# 02-USER_IO.net
KiCad netlist of a schematic drawn in Altium Designer
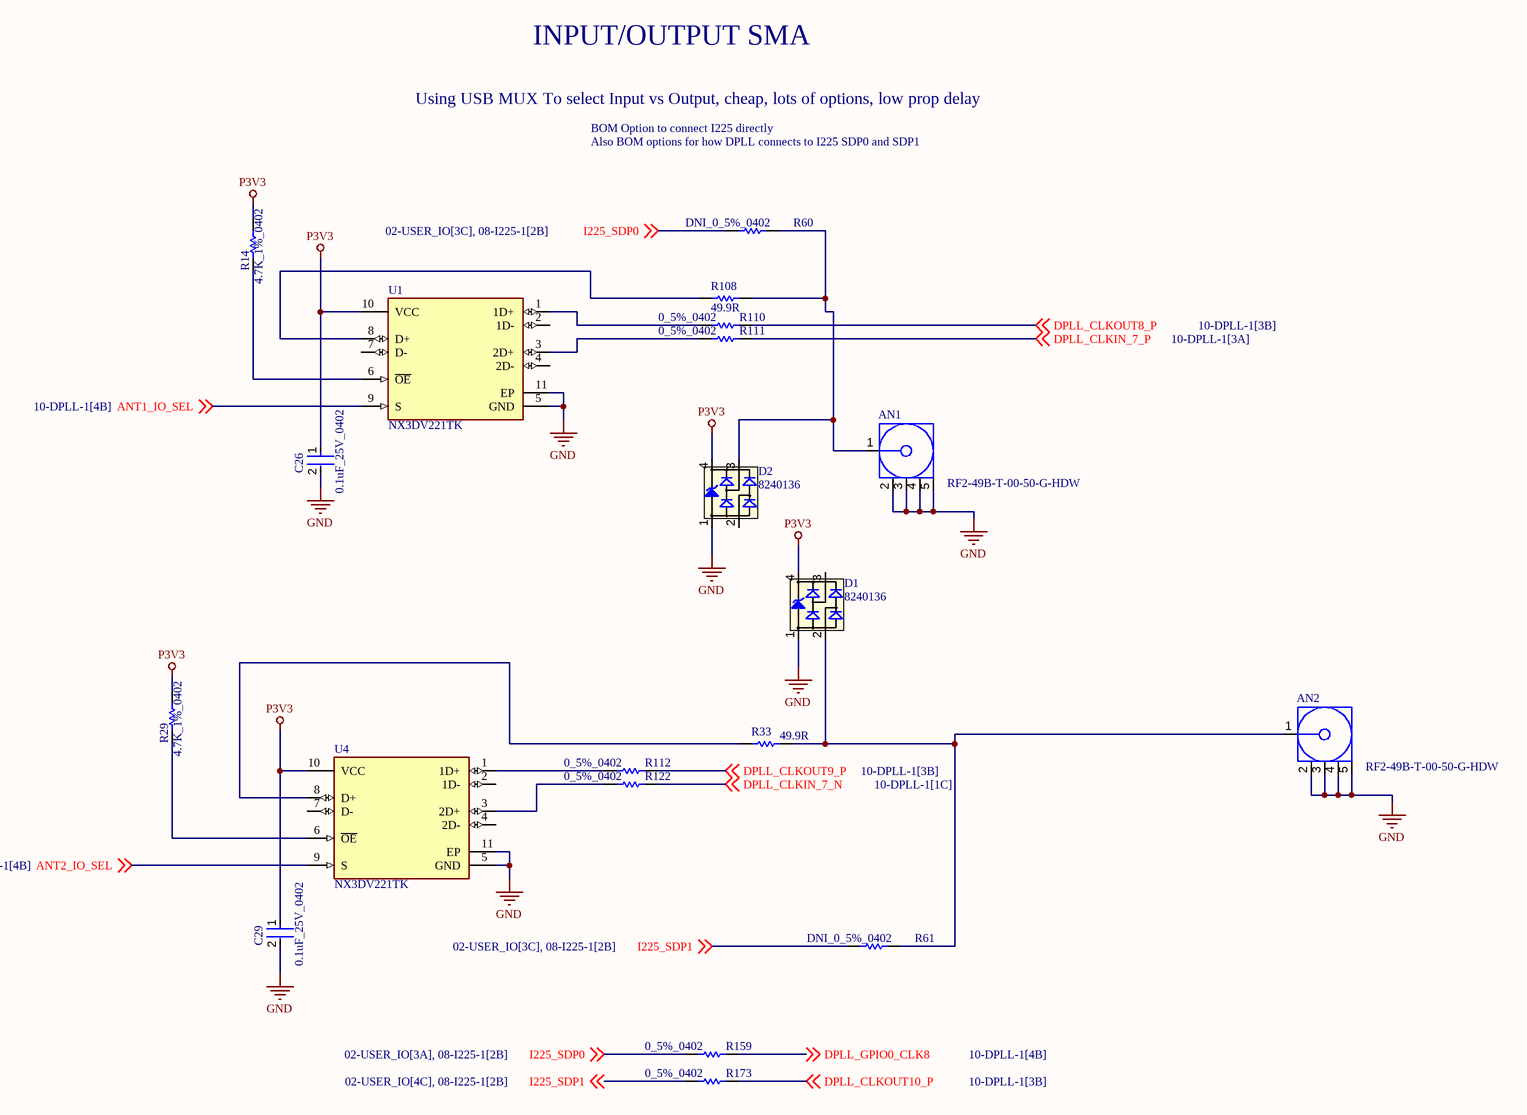
[diagram p0: 02-USER_IO.SchDoc]

(export (version "E")
  (design (tool "Eeschema 10.0.6"))
  (components
    (comp (ref "AN1")
      (value "RF2-49B-T-00-50-G-HDW")
      (footprint "AMPH-901-143-6RFX_V")
      (description "Coaxial connector, 50 Ohm, -65 to 165 degC, 5-Pin THD, RoHS, Bulk")
      (fields (field (name "MANUFACTURER") "Amphenol"))
      (libsource (lib "Altium Content Vault") (part "CN-S-4F-RF5"))
    )
    (comp (ref "AN2")
      (value "RF2-49B-T-00-50-G-HDW")
      (footprint "AMPH-901-143-6RFX_V")
      (description "Coaxial connector, 50 Ohm, -65 to 165 degC, 5-Pin THD, RoHS, Bulk")
      (fields (field (name "MANUFACTURER") "Amphenol"))
      (libsource (lib "Altium Content Vault") (part "CN-S-4F-RF5"))
    )
    (comp (ref "C26")
      (value "0.1uF_25V_0402")
      (footprint "FP-0402-L_1_0_1-W_0_5_0_1-IPC_C")
      (description "General Purpose Ceramic Capacitor, 0402, 100nF, 10%, X7R, 15%, 25V")
      (fields (field (name "VOLTAGE") "25V") (field (name "TOLERANCE") "10%"))
      (libsource (lib "Altium Content Vault") (part "b4654b650e69147ec39a6b967a45e02"))
    )
    (comp (ref "C29")
      (value "0.1uF_25V_0402")
      (footprint "FP-0402-L_1_0_1-W_0_5_0_1-IPC_C")
      (description "General Purpose Ceramic Capacitor, 0402, 100nF, 10%, X7R, 15%, 25V")
      (fields (field (name "VOLTAGE") "25V") (field (name "TOLERANCE") "10%"))
      (libsource (lib "Altium Content Vault") (part "b4654b650e69147ec39a6b967a45e02"))
    )
    (comp (ref "D1")
      (value "8240136")
      (footprint "SOT143-4L")
      (description "TVS Diode WE-TVS-HS, VRWM=3.3V")
      (fields (field (name "MANUFACTURER") "Wuerth Elektronik"))
      (libsource (lib "Altium Content Vault") (part "WE-TVS-HS-4"))
    )
    (comp (ref "D2")
      (value "8240136")
      (footprint "SOT143-4L")
      (description "TVS Diode WE-TVS-HS, VRWM=3.3V")
      (fields (field (name "MANUFACTURER") "Wuerth Elektronik"))
      (libsource (lib "Altium Content Vault") (part "WE-TVS-HS-4"))
    )
    (comp (ref "R14")
      (value "4.7K_1%_0402")
      (footprint "RESC1005X40X25NL10T10")
      (fields (field (name "MANUFACTURER") "Bourns") (field (name "PART NUMBER") "CR0402-FX-4701GLF"))
      (libsource (lib "Altium Content Vault") (part "RES"))
    )
    (comp (ref "R29")
      (value "4.7K_1%_0402")
      (footprint "RESC1005X40X25NL10T10")
      (fields (field (name "MANUFACTURER") "Bourns") (field (name "PART NUMBER") "CR0402-FX-4701GLF"))
      (libsource (lib "Altium Content Vault") (part "RES"))
    )
    (comp (ref "R33")
      (value "49.9R")
      (footprint "RESC1608X55X25NL10T15")
      (libsource (lib "Altium Content Vault") (part "RES-2"))
    )
    (comp (ref "R60")
      (value "DNI_0_5%_0402")
      (footprint "RESC1005X40X25LL10T10")
      (fields (field (name "MANUFACTURER") "KOA Speer") (field (name "PART NUMBER") "RK73Z1ETTP"))
      (libsource (lib "Altium Content Vault") (part "RES"))
    )
    (comp (ref "R61")
      (value "DNI_0_5%_0402")
      (footprint "RESC1005X40X25LL10T10")
      (fields (field (name "MANUFACTURER") "KOA Speer") (field (name "PART NUMBER") "RK73Z1ETTP"))
      (libsource (lib "Altium Content Vault") (part "RES"))
    )
    (comp (ref "R108")
      (value "49.9R")
      (footprint "RESC1608X55X25NL10T15")
      (libsource (lib "Altium Content Vault") (part "RES-2"))
    )
    (comp (ref "R110")
      (value "0_5%_0402")
      (footprint "RESC1005X40X25LL10T10")
      (fields (field (name "MANUFACTURER") "KOA Speer") (field (name "PART NUMBER") "RK73Z1ETTP"))
      (libsource (lib "Altium Content Vault") (part "RES"))
    )
    (comp (ref "R111")
      (value "0_5%_0402")
      (footprint "RESC1005X40X25LL10T10")
      (fields (field (name "MANUFACTURER") "KOA Speer") (field (name "PART NUMBER") "RK73Z1ETTP"))
      (libsource (lib "Altium Content Vault") (part "RES"))
    )
    (comp (ref "R112")
      (value "0_5%_0402")
      (footprint "RESC1005X40X25LL10T10")
      (fields (field (name "MANUFACTURER") "KOA Speer") (field (name "PART NUMBER") "RK73Z1ETTP"))
      (libsource (lib "Altium Content Vault") (part "RES"))
    )
    (comp (ref "R122")
      (value "0_5%_0402")
      (footprint "RESC1005X40X25LL10T10")
      (fields (field (name "MANUFACTURER") "KOA Speer") (field (name "PART NUMBER") "RK73Z1ETTP"))
      (libsource (lib "Altium Content Vault") (part "RES"))
    )
    (comp (ref "R159")
      (value "0_5%_0402")
      (footprint "RESC1005X40X25LL10T10")
      (fields (field (name "MANUFACTURER") "KOA Speer") (field (name "PART NUMBER") "RK73Z1ETTP"))
      (libsource (lib "Altium Content Vault") (part "RES"))
    )
    (comp (ref "R173")
      (value "0_5%_0402")
      (footprint "RESC1005X40X25LL10T10")
      (fields (field (name "MANUFACTURER") "KOA Speer") (field (name "PART NUMBER") "RK73Z1ETTP"))
      (libsource (lib "Altium Content Vault") (part "RES"))
    )
    (comp (ref "U1")
      (value "NX3DV221TK")
      (footprint "FP-SOT650-2-MFG")
      (description "USB Switch IC 1 Channel 10-HVSON (3x3)")
      (libsource (lib "Altium Content Vault") (part "bce77ec48a709d17f0bdc2c26d779bf"))
    )
    (comp (ref "U4")
      (value "NX3DV221TK")
      (footprint "FP-SOT650-2-MFG")
      (description "USB Switch IC 1 Channel 10-HVSON (3x3)")
      (libsource (lib "Altium Content Vault") (part "bce77ec48a709d17f0bdc2c26d779bf"))
    )
  )
  (nets
    (net (code "1") (name "ANT1_IO_SEL") (class "Default")
      (node (ref "U1") (pin "9") (pinfunction "S_9") (pintype "input"))
    )
    (net (code "2") (name "ANT2_IO_SEL") (class "Default")
      (node (ref "U4") (pin "9") (pinfunction "S_9") (pintype "input"))
    )
    (net (code "3") (name "DPLL_CLKIN_7_N") (class "Default")
      (node (ref "R122") (pin "2") (pinfunction "2_2") (pintype "passive"))
    )
    (net (code "4") (name "DPLL_CLKIN_7_P") (class "Default")
      (node (ref "R111") (pin "2") (pinfunction "2_2") (pintype "passive"))
    )
    (net (code "5") (name "DPLL_CLKOUT8_P") (class "Default")
      (node (ref "R110") (pin "2") (pinfunction "2_2") (pintype "passive"))
    )
    (net (code "6") (name "DPLL_CLKOUT9_P") (class "Default")
      (node (ref "R112") (pin "2") (pinfunction "2_2") (pintype "passive"))
    )
    (net (code "7") (name "DPLL_CLKOUT10_P") (class "Default")
      (node (ref "R173") (pin "2") (pinfunction "2_2") (pintype "passive"))
    )
    (net (code "8") (name "DPLL_GPIO0_CLK8") (class "Default")
      (node (ref "R159") (pin "2") (pinfunction "2_2") (pintype "passive"))
    )
    (net (code "9") (name "GND") (class "Default")
      (node (ref "AN1") (pin "2") (pinfunction "2_2") (pintype "passive"))
      (node (ref "AN1") (pin "3") (pinfunction "3_3") (pintype "passive"))
      (node (ref "AN1") (pin "4") (pinfunction "4_4") (pintype "passive"))
      (node (ref "AN1") (pin "5") (pinfunction "5_5") (pintype "passive"))
      (node (ref "AN2") (pin "2") (pinfunction "2_2") (pintype "passive"))
      (node (ref "AN2") (pin "3") (pinfunction "3_3") (pintype "passive"))
      (node (ref "AN2") (pin "4") (pinfunction "4_4") (pintype "passive"))
      (node (ref "AN2") (pin "5") (pinfunction "5_5") (pintype "passive"))
      (node (ref "C26") (pin "2") (pinfunction "2_2") (pintype "passive"))
      (node (ref "C29") (pin "2") (pinfunction "2_2") (pintype "passive"))
      (node (ref "D1") (pin "1") (pinfunction "GND_1") (pintype "passive"))
      (node (ref "D2") (pin "1") (pinfunction "GND_1") (pintype "passive"))
      (node (ref "U1") (pin "11") (pinfunction "EP_11") (pintype "passive"))
      (node (ref "U1") (pin "5") (pinfunction "GND_5") (pintype "power_in"))
      (node (ref "U4") (pin "11") (pinfunction "EP_11") (pintype "passive"))
      (node (ref "U4") (pin "5") (pinfunction "GND_5") (pintype "power_in"))
    )
    (net (code "10") (name "I225_SDP0") (class "Default")
      (node (ref "R159") (pin "1") (pinfunction "1_1") (pintype "passive"))
      (node (ref "R60") (pin "1") (pinfunction "1_1") (pintype "passive"))
    )
    (net (code "11") (name "I225_SDP1") (class "Default")
      (node (ref "R173") (pin "1") (pinfunction "1_1") (pintype "passive"))
      (node (ref "R61") (pin "1") (pinfunction "1_1") (pintype "passive"))
    )
    (net (code "12") (name "Net-(D1-I{slash}O1)") (class "Default")
      (node (ref "AN2") (pin "1") (pinfunction "1_1") (pintype "passive"))
      (node (ref "D1") (pin "2") (pinfunction "I/O1_2") (pintype "passive"))
      (node (ref "R33") (pin "2") (pinfunction "2_2") (pintype "passive"))
      (node (ref "R61") (pin "2") (pinfunction "2_2") (pintype "passive"))
    )
    (net (code "13") (name "Net-(D2-I{slash}O2)") (class "Default")
      (node (ref "AN1") (pin "1") (pinfunction "1_1") (pintype "passive"))
      (node (ref "D2") (pin "3") (pinfunction "I/O2_3") (pintype "passive"))
      (node (ref "R108") (pin "1") (pinfunction "1_1") (pintype "passive"))
      (node (ref "R60") (pin "2") (pinfunction "2_2") (pintype "passive"))
    )
    (net (code "14") (name "Net-(U1-1D+)") (class "Default")
      (node (ref "R110") (pin "1") (pinfunction "1_1") (pintype "passive"))
      (node (ref "U1") (pin "1") (pinfunction "1D+_1") (pintype "bidirectional"))
    )
    (net (code "15") (name "Net-(U1-2D+)") (class "Default")
      (node (ref "R111") (pin "1") (pinfunction "1_1") (pintype "passive"))
      (node (ref "U1") (pin "3") (pinfunction "2D+_3") (pintype "bidirectional"))
    )
    (net (code "16") (name "Net-(U1-D+)") (class "Default")
      (node (ref "R108") (pin "2") (pinfunction "2_2") (pintype "passive"))
      (node (ref "U1") (pin "8") (pinfunction "D+_8") (pintype "bidirectional"))
    )
    (net (code "17") (name "Net-(U1-~{OE})") (class "Default")
      (node (ref "R14") (pin "2") (pinfunction "2_2") (pintype "passive"))
      (node (ref "U1") (pin "6") (pinfunction "~{OE}_6") (pintype "input"))
    )
    (net (code "18") (name "Net-(U4-1D+)") (class "Default")
      (node (ref "R112") (pin "1") (pinfunction "1_1") (pintype "passive"))
      (node (ref "U4") (pin "1") (pinfunction "1D+_1") (pintype "bidirectional"))
    )
    (net (code "19") (name "Net-(U4-2D+)") (class "Default")
      (node (ref "R122") (pin "1") (pinfunction "1_1") (pintype "passive"))
      (node (ref "U4") (pin "3") (pinfunction "2D+_3") (pintype "bidirectional"))
    )
    (net (code "20") (name "Net-(U4-D+)") (class "Default")
      (node (ref "R33") (pin "1") (pinfunction "1_1") (pintype "passive"))
      (node (ref "U4") (pin "8") (pinfunction "D+_8") (pintype "bidirectional"))
    )
    (net (code "21") (name "Net-(U4-~{OE})") (class "Default")
      (node (ref "R29") (pin "2") (pinfunction "2_2") (pintype "passive"))
      (node (ref "U4") (pin "6") (pinfunction "~{OE}_6") (pintype "input"))
    )
    (net (code "22") (name "P3V3") (class "Default")
      (node (ref "C26") (pin "1") (pinfunction "1_1") (pintype "passive"))
      (node (ref "C29") (pin "1") (pinfunction "1_1") (pintype "passive"))
      (node (ref "D1") (pin "4") (pinfunction "VDD_4") (pintype "passive"))
      (node (ref "D2") (pin "4") (pinfunction "VDD_4") (pintype "passive"))
      (node (ref "R14") (pin "1") (pinfunction "1_1") (pintype "passive"))
      (node (ref "R29") (pin "1") (pinfunction "1_1") (pintype "passive"))
      (node (ref "U1") (pin "10") (pinfunction "VCC_10") (pintype "power_in"))
      (node (ref "U4") (pin "10") (pinfunction "VCC_10") (pintype "power_in"))
    )
    (net (code "23") (name "unconnected-(D1-I{slash}O2-Pad3)") (class "Default")
      (node (ref "D1") (pin "3") (pinfunction "I/O2_3") (pintype "passive"))
    )
    (net (code "24") (name "unconnected-(D2-I{slash}O1-Pad2)") (class "Default")
      (node (ref "D2") (pin "2") (pinfunction "I/O1_2") (pintype "passive"))
    )
    (net (code "25") (name "unconnected-(U1-1D--Pad2)") (class "Default")
      (node (ref "U1") (pin "2") (pinfunction "1D-_2") (pintype "bidirectional"))
    )
    (net (code "26") (name "unconnected-(U1-2D--Pad4)") (class "Default")
      (node (ref "U1") (pin "4") (pinfunction "2D-_4") (pintype "bidirectional"))
    )
    (net (code "27") (name "unconnected-(U1-D--Pad7)") (class "Default")
      (node (ref "U1") (pin "7") (pinfunction "D-_7") (pintype "bidirectional"))
    )
    (net (code "28") (name "unconnected-(U4-1D--Pad2)") (class "Default")
      (node (ref "U4") (pin "2") (pinfunction "1D-_2") (pintype "bidirectional"))
    )
    (net (code "29") (name "unconnected-(U4-2D--Pad4)") (class "Default")
      (node (ref "U4") (pin "4") (pinfunction "2D-_4") (pintype "bidirectional"))
    )
    (net (code "30") (name "unconnected-(U4-D--Pad7)") (class "Default")
      (node (ref "U4") (pin "7") (pinfunction "D-_7") (pintype "bidirectional"))
    )
  )
)
